# Sheet1.net
KiCad netlist of a schematic drawn in Altium Designer
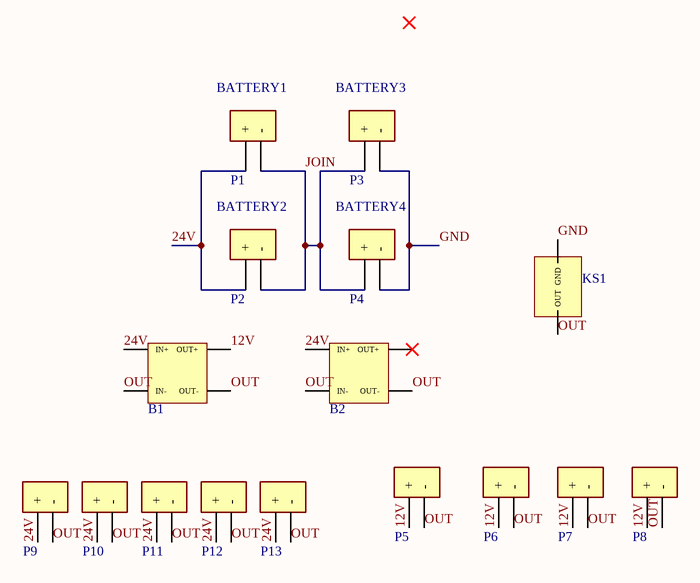
[diagram p0: Sheet1.SchDoc]

(export (version "E")
  (design (tool "Eeschema 10.0.6"))
  (components
    (comp (ref "B1") (value "BUCK") (footprint "BUCK") (libsource (lib "BUCK") (part "BUCK")))
    (comp (ref "B2") (value "BUCK") (footprint "BUCK") (libsource (lib "BUCK") (part "BUCK")))
    (comp (ref "KS1") (value "KS") (footprint "KS") (libsource (lib "BUCK") (part "KS")))
    (comp (ref "P1")
      (value "BATTERY1")
      (footprint "TE_282837-2")
      (fields (field (name "MF") "TE Connectivity") (field (name "MP") "282837-2"))
      (libsource (lib "282837-2") (part "282837-2"))
    )
    (comp (ref "P2")
      (value "BATTERY2")
      (footprint "TE_282837-2")
      (fields (field (name "MF") "TE Connectivity") (field (name "MP") "282837-2"))
      (libsource (lib "282837-2") (part "282837-2"))
    )
    (comp (ref "P3")
      (value "BATTERY3")
      (footprint "TE_282837-2")
      (fields (field (name "MF") "TE Connectivity") (field (name "MP") "282837-2"))
      (libsource (lib "282837-2") (part "282837-2"))
    )
    (comp (ref "P4")
      (value "BATTERY4")
      (footprint "TE_282837-2")
      (fields (field (name "MF") "TE Connectivity") (field (name "MP") "282837-2"))
      (libsource (lib "282837-2") (part "282837-2"))
    )
    (comp (ref "P5")
      (value "282837-2")
      (footprint "TE_282837-2")
      (fields (field (name "MF") "TE Connectivity"))
      (libsource (lib "282837-2") (part "282837-2"))
    )
    (comp (ref "P6")
      (value "282837-2")
      (footprint "TE_282837-2")
      (fields (field (name "MF") "TE Connectivity"))
      (libsource (lib "282837-2") (part "282837-2"))
    )
    (comp (ref "P7")
      (value "282837-2")
      (footprint "TE_282837-2")
      (fields (field (name "MF") "TE Connectivity"))
      (libsource (lib "282837-2") (part "282837-2"))
    )
    (comp (ref "P8")
      (value "282837-2")
      (footprint "TE_282837-2")
      (fields (field (name "MF") "TE Connectivity"))
      (libsource (lib "282837-2") (part "282837-2"))
    )
    (comp (ref "P9")
      (value "282837-2")
      (footprint "TE_282837-2")
      (fields (field (name "MF") "TE Connectivity"))
      (libsource (lib "282837-2") (part "282837-2"))
    )
    (comp (ref "P10")
      (value "282837-2")
      (footprint "TE_282837-2")
      (fields (field (name "MF") "TE Connectivity"))
      (libsource (lib "282837-2") (part "282837-2"))
    )
    (comp (ref "P11")
      (value "282837-2")
      (footprint "TE_282837-2")
      (fields (field (name "MF") "TE Connectivity"))
      (libsource (lib "282837-2") (part "282837-2"))
    )
    (comp (ref "P12")
      (value "282837-2")
      (footprint "TE_282837-2")
      (fields (field (name "MF") "TE Connectivity"))
      (libsource (lib "282837-2") (part "282837-2"))
    )
    (comp (ref "P13")
      (value "282837-2")
      (footprint "TE_282837-2")
      (fields (field (name "MF") "TE Connectivity"))
      (libsource (lib "282837-2") (part "282837-2"))
    )
  )
  (nets
    (net (code "1") (name "/12V") (class "Default")
      (node (ref "B1") (pin "3") (pinfunction "OUT+_3") (pintype "passive"))
      (node (ref "P5") (pin "1") (pinfunction "+_1") (pintype "passive"))
      (node (ref "P6") (pin "1") (pinfunction "+_1") (pintype "passive"))
      (node (ref "P7") (pin "1") (pinfunction "+_1") (pintype "passive"))
      (node (ref "P8") (pin "1") (pinfunction "+_1") (pintype "passive"))
    )
    (net (code "2") (name "/24V") (class "Default")
      (node (ref "B1") (pin "1") (pinfunction "IN+_1") (pintype "passive"))
      (node (ref "B2") (pin "1") (pinfunction "IN+_1") (pintype "passive"))
      (node (ref "P1") (pin "1") (pinfunction "+_1") (pintype "passive"))
      (node (ref "P10") (pin "1") (pinfunction "+_1") (pintype "passive"))
      (node (ref "P11") (pin "1") (pinfunction "+_1") (pintype "passive"))
      (node (ref "P12") (pin "1") (pinfunction "+_1") (pintype "passive"))
      (node (ref "P13") (pin "1") (pinfunction "+_1") (pintype "passive"))
      (node (ref "P2") (pin "1") (pinfunction "+_1") (pintype "passive"))
      (node (ref "P9") (pin "1") (pinfunction "+_1") (pintype "passive"))
    )
    (net (code "3") (name "/GND") (class "Default")
      (node (ref "KS1") (pin "1") (pinfunction "GND_1") (pintype "passive"))
      (node (ref "P3") (pin "2") (pinfunction "-_2") (pintype "passive"))
      (node (ref "P4") (pin "2") (pinfunction "-_2") (pintype "passive"))
    )
    (net (code "4") (name "/JOIN") (class "Default")
      (node (ref "P1") (pin "2") (pinfunction "-_2") (pintype "passive"))
      (node (ref "P2") (pin "2") (pinfunction "-_2") (pintype "passive"))
      (node (ref "P3") (pin "1") (pinfunction "+_1") (pintype "passive"))
      (node (ref "P4") (pin "1") (pinfunction "+_1") (pintype "passive"))
    )
    (net (code "5") (name "/OUT") (class "Default")
      (node (ref "B1") (pin "2") (pinfunction "IN-_2") (pintype "passive"))
      (node (ref "B1") (pin "4") (pinfunction "OUT-_4") (pintype "passive"))
      (node (ref "B2") (pin "2") (pinfunction "IN-_2") (pintype "passive"))
      (node (ref "B2") (pin "4") (pinfunction "OUT-_4") (pintype "passive"))
      (node (ref "KS1") (pin "2") (pinfunction "OUT_2") (pintype "passive"))
      (node (ref "P10") (pin "2") (pinfunction "-_2") (pintype "passive"))
      (node (ref "P11") (pin "2") (pinfunction "-_2") (pintype "passive"))
      (node (ref "P12") (pin "2") (pinfunction "-_2") (pintype "passive"))
      (node (ref "P13") (pin "2") (pinfunction "-_2") (pintype "passive"))
      (node (ref "P5") (pin "2") (pinfunction "-_2") (pintype "passive"))
      (node (ref "P6") (pin "2") (pinfunction "-_2") (pintype "passive"))
      (node (ref "P7") (pin "2") (pinfunction "-_2") (pintype "passive"))
      (node (ref "P8") (pin "2") (pinfunction "-_2") (pintype "passive"))
      (node (ref "P9") (pin "2") (pinfunction "-_2") (pintype "passive"))
    )
    (net (code "6") (name "unconnected-(B2-OUT+-Pad3)") (class "Default")
      (node (ref "B2") (pin "3") (pinfunction "OUT+_3") (pintype "passive+no_connect"))
    )
  )
)
